# FPGA_USB.net
KiCad netlist of a schematic drawn in Altium Designer
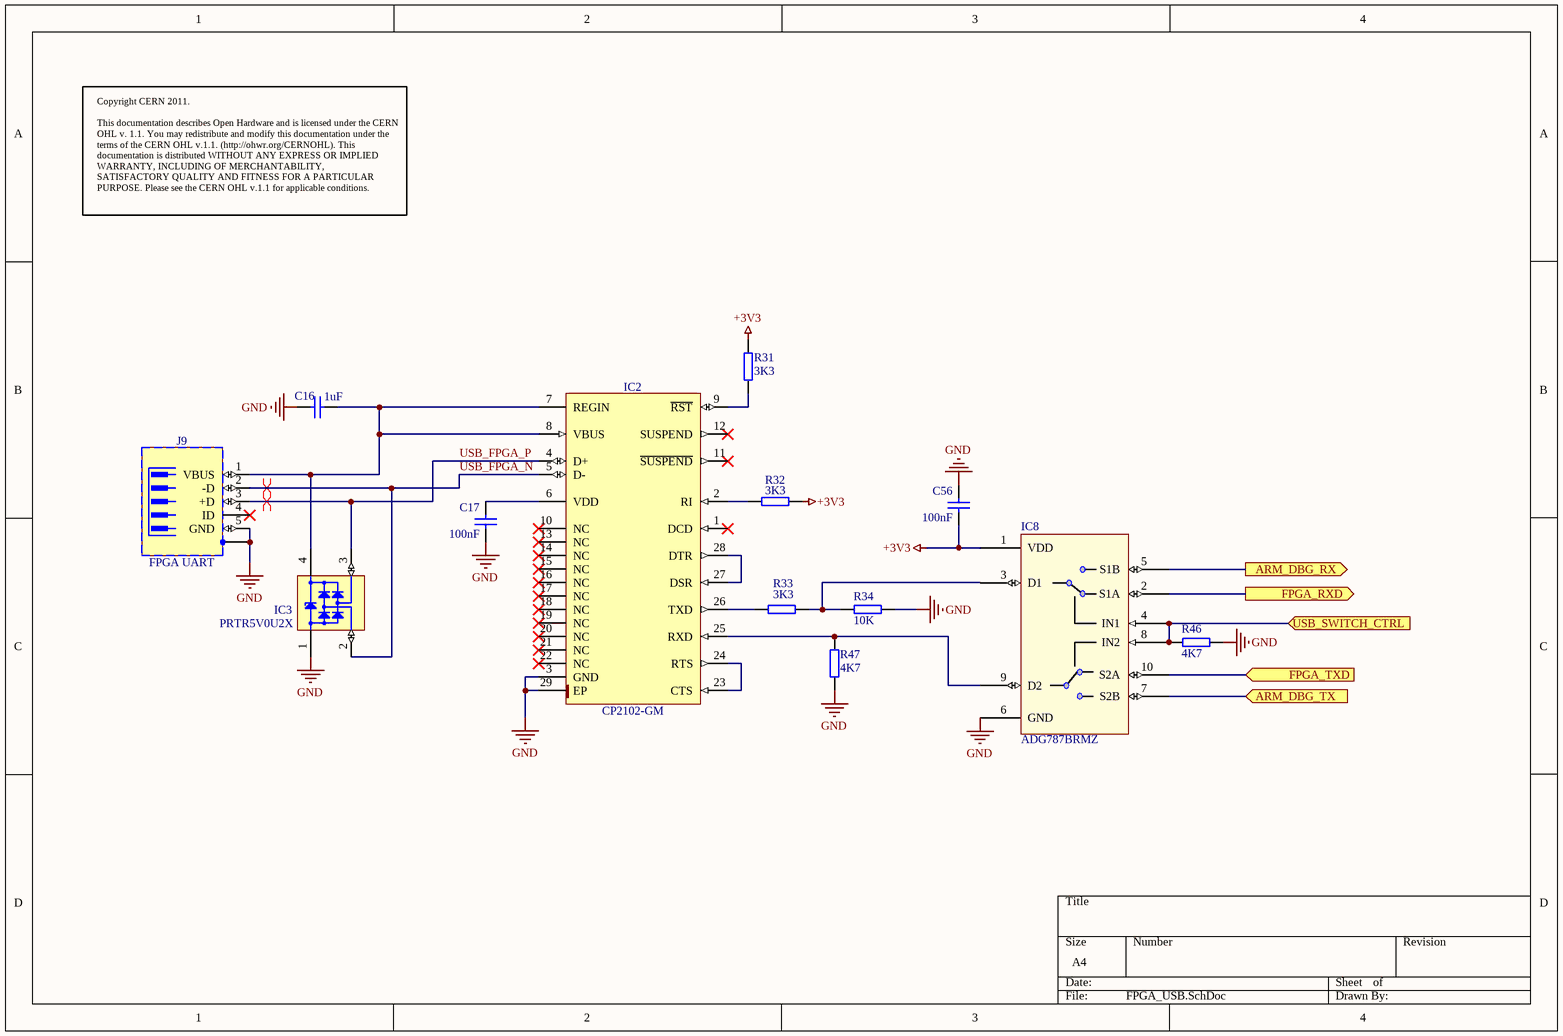
[diagram p0: FPGA_USB.SchDoc]

(export (version "E")
  (design (tool "Eeschema 10.0.6"))
  (components
    (comp (ref "C16")
      (value "1uF")
      (footprint "CC1608-0603")
      (description "Capacitor")
      (fields
        (field (name "TOLERANCE") "±10%")
        (field (name "VOLTAGE") "25V")
        (field (name "PUBLISHER") "Altium Limited")
      )
      (libsource (lib "wr_switch") (part "Cap"))
    )
    (comp (ref "C17")
      (value "100nF")
      (footprint "CC1608-0603")
      (description "Capacitor")
      (fields
        (field (name "TOLERANCE") "±10%")
        (field (name "VOLTAGE") "16V")
        (field (name "PUBLISHER") "Altium Limited")
      )
      (libsource (lib "wr_switch") (part "Cap"))
    )
    (comp (ref "C56")
      (value "100nF")
      (footprint "CC1608-0603")
      (description "Capacitor")
      (fields
        (field (name "TOLERANCE") "±10%")
        (field (name "VOLTAGE") "16V")
        (field (name "PUBLISHER") "Altium Limited")
      )
      (libsource (lib "wr_switch") (part "Cap"))
    )
    (comp (ref "IC2")
      (value "CP2102-GM")
      (footprint "7S_WR:QFN50P500X500X100-29N-S335")
      (description "Single-Chip USB to UART Bridge")
      (fields (field (name "MANUFACTURER") "SILICON LABS") (field (name "AUTHOR") "CERN DEM JLC"))
      (libsource (lib "wr_switch") (part "CP2102-GM"))
    )
    (comp (ref "IC3")
      (value "PRTR5V0U2X")
      (footprint "7S_WR:SOT190P230X110-4N")
      (description "Ultra Low Capacitance Double Rail-to-Rail ESD Protection Diode")
      (fields
        (field (name "VOLTAGE") "5.5V")
        (field (name "MANUFACTURER") "PHILIPS NXP")
        (field (name "AUTHOR") "CERN DEM JLC")
      )
      (libsource (lib "wr_switch") (part "PRTR5V0U2X"))
    )
    (comp (ref "IC8")
      (value "ADG787BRMZ")
      (footprint "SOP50P490X109-10N")
      (description "Dual 2:1 MUX/DEMUX USB1.1 Switch")
      (libsource (lib "wr_switch") (part "ADG787BRMZ"))
    )
    (comp (ref "J9")
      (value "FPGA UART")
      (footprint "7S_WR:TYCO_1734035-1")
      (description "5 Pin + 1 Shield Mini USB Type B Receptacle")
      (fields
        (field (name "PART NUMBER") "TYCO_1734035-1")
        (field (name "MANUFACTURER") "TYCO ELECTRONICS")
        (field (name "AUTHOR") "CERN DEM JLC")
      )
      (libsource (lib "wr_switch") (part "TYCO_1734035-1"))
    )
    (comp (ref "R31")
      (value "3K3")
      (footprint "0603")
      (description "SMD Resistor")
      (fields (field (name "TOLERANCE") "±1%"))
      (libsource (lib "wr_switch") (part "RES_SMD"))
    )
    (comp (ref "R32")
      (value "3K3")
      (footprint "0603")
      (description "SMD Resistor")
      (fields (field (name "TOLERANCE") "±1%"))
      (libsource (lib "wr_switch") (part "RES_SMD"))
    )
    (comp (ref "R33")
      (value "3K3")
      (footprint "0603")
      (description "SMD Resistor")
      (fields (field (name "TOLERANCE") "±1%"))
      (libsource (lib "wr_switch") (part "RES_SMD"))
    )
    (comp (ref "R34")
      (value "10K")
      (footprint "0603")
      (description "SMD Resistor")
      (fields (field (name "TOLERANCE") "±1%"))
      (libsource (lib "wr_switch") (part "RES_SMD"))
    )
    (comp (ref "R46")
      (value "4K7")
      (footprint "0603")
      (description "SMD Resistor")
      (fields (field (name "TOLERANCE") "±1%"))
      (libsource (lib "wr_switch") (part "RES_SMD"))
    )
    (comp (ref "R47")
      (value "4K7")
      (footprint "0603")
      (description "SMD Resistor")
      (fields (field (name "TOLERANCE") "±1%"))
      (libsource (lib "wr_switch") (part "RES_SMD"))
    )
  )
  (nets
    (net (code "1") (name "+3V3") (class "Default")
      (node (ref "C56") (pin "2") (pinfunction "2_2") (pintype "passive"))
      (node (ref "IC8") (pin "1") (pinfunction "VDD_1") (pintype "power_in"))
      (node (ref "R31") (pin "2") (pinfunction "2_2") (pintype "passive"))
      (node (ref "R32") (pin "2") (pinfunction "2_2") (pintype "passive"))
    )
    (net (code "2") (name "/ARM_DBG_RX") (class "Default")
      (node (ref "IC8") (pin "5") (pinfunction "S1B_5") (pintype "bidirectional"))
    )
    (net (code "3") (name "/ARM_DBG_TX") (class "Default")
      (node (ref "IC8") (pin "7") (pinfunction "S2B_7") (pintype "bidirectional"))
    )
    (net (code "4") (name "/FPGA_RXD") (class "Default")
      (node (ref "IC8") (pin "2") (pinfunction "S1A_2") (pintype "bidirectional"))
    )
    (net (code "5") (name "/FPGA_TXD") (class "Default")
      (node (ref "IC8") (pin "10") (pinfunction "S2A_10") (pintype "bidirectional"))
    )
    (net (code "6") (name "/USB_FPGA_N") (class "Default")
      (node (ref "IC2") (pin "5") (pinfunction "D-_5") (pintype "bidirectional"))
      (node (ref "IC3") (pin "2") (pinfunction "I/O1_2") (pintype "bidirectional"))
      (node (ref "J9") (pin "2") (pinfunction "-D_2") (pintype "bidirectional"))
    )
    (net (code "7") (name "/USB_FPGA_P") (class "Default")
      (node (ref "IC2") (pin "4") (pinfunction "D+_4") (pintype "bidirectional"))
      (node (ref "IC3") (pin "3") (pinfunction "I/O2_3") (pintype "bidirectional"))
      (node (ref "J9") (pin "3") (pinfunction "+D_3") (pintype "bidirectional"))
    )
    (net (code "8") (name "/USB_SWITCH_CTRL") (class "Default")
      (node (ref "IC8") (pin "4") (pinfunction "IN1_4") (pintype "input"))
      (node (ref "IC8") (pin "8") (pinfunction "IN2_8") (pintype "input"))
      (node (ref "R46") (pin "2") (pinfunction "2_2") (pintype "passive"))
    )
    (net (code "9") (name "GND") (class "Default")
      (node (ref "C16") (pin "1") (pinfunction "1_1") (pintype "passive"))
      (node (ref "C17") (pin "2") (pinfunction "2_2") (pintype "passive"))
      (node (ref "C56") (pin "1") (pinfunction "1_1") (pintype "passive"))
      (node (ref "IC2") (pin "29") (pinfunction "EP_29") (pintype "power_in"))
      (node (ref "IC2") (pin "3") (pinfunction "GND_3") (pintype "power_in"))
      (node (ref "IC3") (pin "1") (pinfunction "GND_1") (pintype "power_in"))
      (node (ref "IC8") (pin "6") (pinfunction "GND_6") (pintype "power_in"))
      (node (ref "J9") (pin "5") (pinfunction "GND_5") (pintype "bidirectional"))
      (node (ref "J9") (pin "6") (pinfunction "SH_6") (pintype "power_in"))
      (node (ref "R34") (pin "1") (pinfunction "1_1") (pintype "passive"))
      (node (ref "R46") (pin "1") (pinfunction "1_1") (pintype "passive"))
      (node (ref "R47") (pin "2") (pinfunction "2_2") (pintype "passive"))
    )
    (net (code "10") (name "Net-(IC2-CTS)") (class "Default")
      (node (ref "IC2") (pin "23") (pinfunction "CTS_23") (pintype "input"))
      (node (ref "IC2") (pin "24") (pinfunction "RTS_24") (pintype "output"))
    )
    (net (code "11") (name "Net-(IC2-DSR)") (class "Default")
      (node (ref "IC2") (pin "27") (pinfunction "DSR_27") (pintype "input"))
      (node (ref "IC2") (pin "28") (pinfunction "DTR_28") (pintype "output"))
    )
    (net (code "12") (name "Net-(IC2-REGIN)") (class "Default")
      (node (ref "C16") (pin "2") (pinfunction "2_2") (pintype "passive"))
      (node (ref "IC2") (pin "7") (pinfunction "REGIN_7") (pintype "power_in"))
      (node (ref "IC2") (pin "8") (pinfunction "VBUS_8") (pintype "input"))
      (node (ref "IC3") (pin "4") (pinfunction "VCC_4") (pintype "power_in"))
      (node (ref "J9") (pin "1") (pinfunction "VBUS_1") (pintype "bidirectional"))
    )
    (net (code "13") (name "Net-(IC2-RI)") (class "Default")
      (node (ref "IC2") (pin "2") (pinfunction "RI_2") (pintype "input"))
      (node (ref "R32") (pin "1") (pinfunction "1_1") (pintype "passive"))
    )
    (net (code "14") (name "Net-(IC2-RXD)") (class "Default")
      (node (ref "IC2") (pin "25") (pinfunction "RXD_25") (pintype "input"))
      (node (ref "IC8") (pin "9") (pinfunction "D2_9") (pintype "bidirectional"))
      (node (ref "R47") (pin "1") (pinfunction "1_1") (pintype "passive"))
    )
    (net (code "15") (name "Net-(IC2-TXD)") (class "Default")
      (node (ref "IC2") (pin "26") (pinfunction "TXD_26") (pintype "output"))
      (node (ref "R33") (pin "1") (pinfunction "1_1") (pintype "passive"))
    )
    (net (code "16") (name "Net-(IC2-VDD)") (class "Default")
      (node (ref "C17") (pin "1") (pinfunction "1_1") (pintype "passive"))
      (node (ref "IC2") (pin "6") (pinfunction "VDD_6") (pintype "power_in"))
    )
    (net (code "17") (name "Net-(IC2-~{RST})") (class "Default")
      (node (ref "IC2") (pin "9") (pinfunction "~{RST}_9") (pintype "bidirectional"))
      (node (ref "R31") (pin "1") (pinfunction "1_1") (pintype "passive"))
    )
    (net (code "18") (name "Net-(IC8-D1)") (class "Default")
      (node (ref "IC8") (pin "3") (pinfunction "D1_3") (pintype "bidirectional"))
      (node (ref "R33") (pin "2") (pinfunction "2_2") (pintype "passive"))
      (node (ref "R34") (pin "2") (pinfunction "2_2") (pintype "passive"))
    )
    (net (code "19") (name "unconnected-(IC2-DCD-Pad1)") (class "Default")
      (node (ref "IC2") (pin "1") (pinfunction "DCD_1") (pintype "input+no_connect"))
    )
    (net (code "20") (name "unconnected-(IC2-NC-Pad10)") (class "Default")
      (node (ref "IC2") (pin "10") (pinfunction "NC_10") (pintype "passive+no_connect"))
    )
    (net (code "21") (name "unconnected-(IC2-NC-Pad13)") (class "Default")
      (node (ref "IC2") (pin "13") (pinfunction "NC_13") (pintype "passive+no_connect"))
    )
    (net (code "22") (name "unconnected-(IC2-NC-Pad14)") (class "Default")
      (node (ref "IC2") (pin "14") (pinfunction "NC_14") (pintype "passive+no_connect"))
    )
    (net (code "23") (name "unconnected-(IC2-NC-Pad15)") (class "Default")
      (node (ref "IC2") (pin "15") (pinfunction "NC_15") (pintype "passive+no_connect"))
    )
    (net (code "24") (name "unconnected-(IC2-NC-Pad16)") (class "Default")
      (node (ref "IC2") (pin "16") (pinfunction "NC_16") (pintype "passive+no_connect"))
    )
    (net (code "25") (name "unconnected-(IC2-NC-Pad17)") (class "Default")
      (node (ref "IC2") (pin "17") (pinfunction "NC_17") (pintype "passive+no_connect"))
    )
    (net (code "26") (name "unconnected-(IC2-NC-Pad18)") (class "Default")
      (node (ref "IC2") (pin "18") (pinfunction "NC_18") (pintype "passive+no_connect"))
    )
    (net (code "27") (name "unconnected-(IC2-NC-Pad19)") (class "Default")
      (node (ref "IC2") (pin "19") (pinfunction "NC_19") (pintype "passive+no_connect"))
    )
    (net (code "28") (name "unconnected-(IC2-NC-Pad20)") (class "Default")
      (node (ref "IC2") (pin "20") (pinfunction "NC_20") (pintype "passive+no_connect"))
    )
    (net (code "29") (name "unconnected-(IC2-NC-Pad21)") (class "Default")
      (node (ref "IC2") (pin "21") (pinfunction "NC_21") (pintype "passive+no_connect"))
    )
    (net (code "30") (name "unconnected-(IC2-NC-Pad22)") (class "Default")
      (node (ref "IC2") (pin "22") (pinfunction "NC_22") (pintype "passive+no_connect"))
    )
    (net (code "31") (name "unconnected-(IC2-SUSPEND-Pad12)") (class "Default")
      (node (ref "IC2") (pin "12") (pinfunction "SUSPEND_12") (pintype "output+no_connect"))
    )
    (net (code "32") (name "unconnected-(IC2-~{SUSPEND}-Pad11)") (class "Default")
      (node (ref "IC2") (pin "11") (pinfunction "~{SUSPEND}_11") (pintype "output+no_connect"))
    )
    (net (code "33") (name "unconnected-(J9-ID-Pad4)") (class "Default")
      (node (ref "J9") (pin "4") (pinfunction "ID_4") (pintype "passive+no_connect"))
    )
  )
)
